# Sensors.net
KiCad netlist of a schematic drawn in Altium Designer
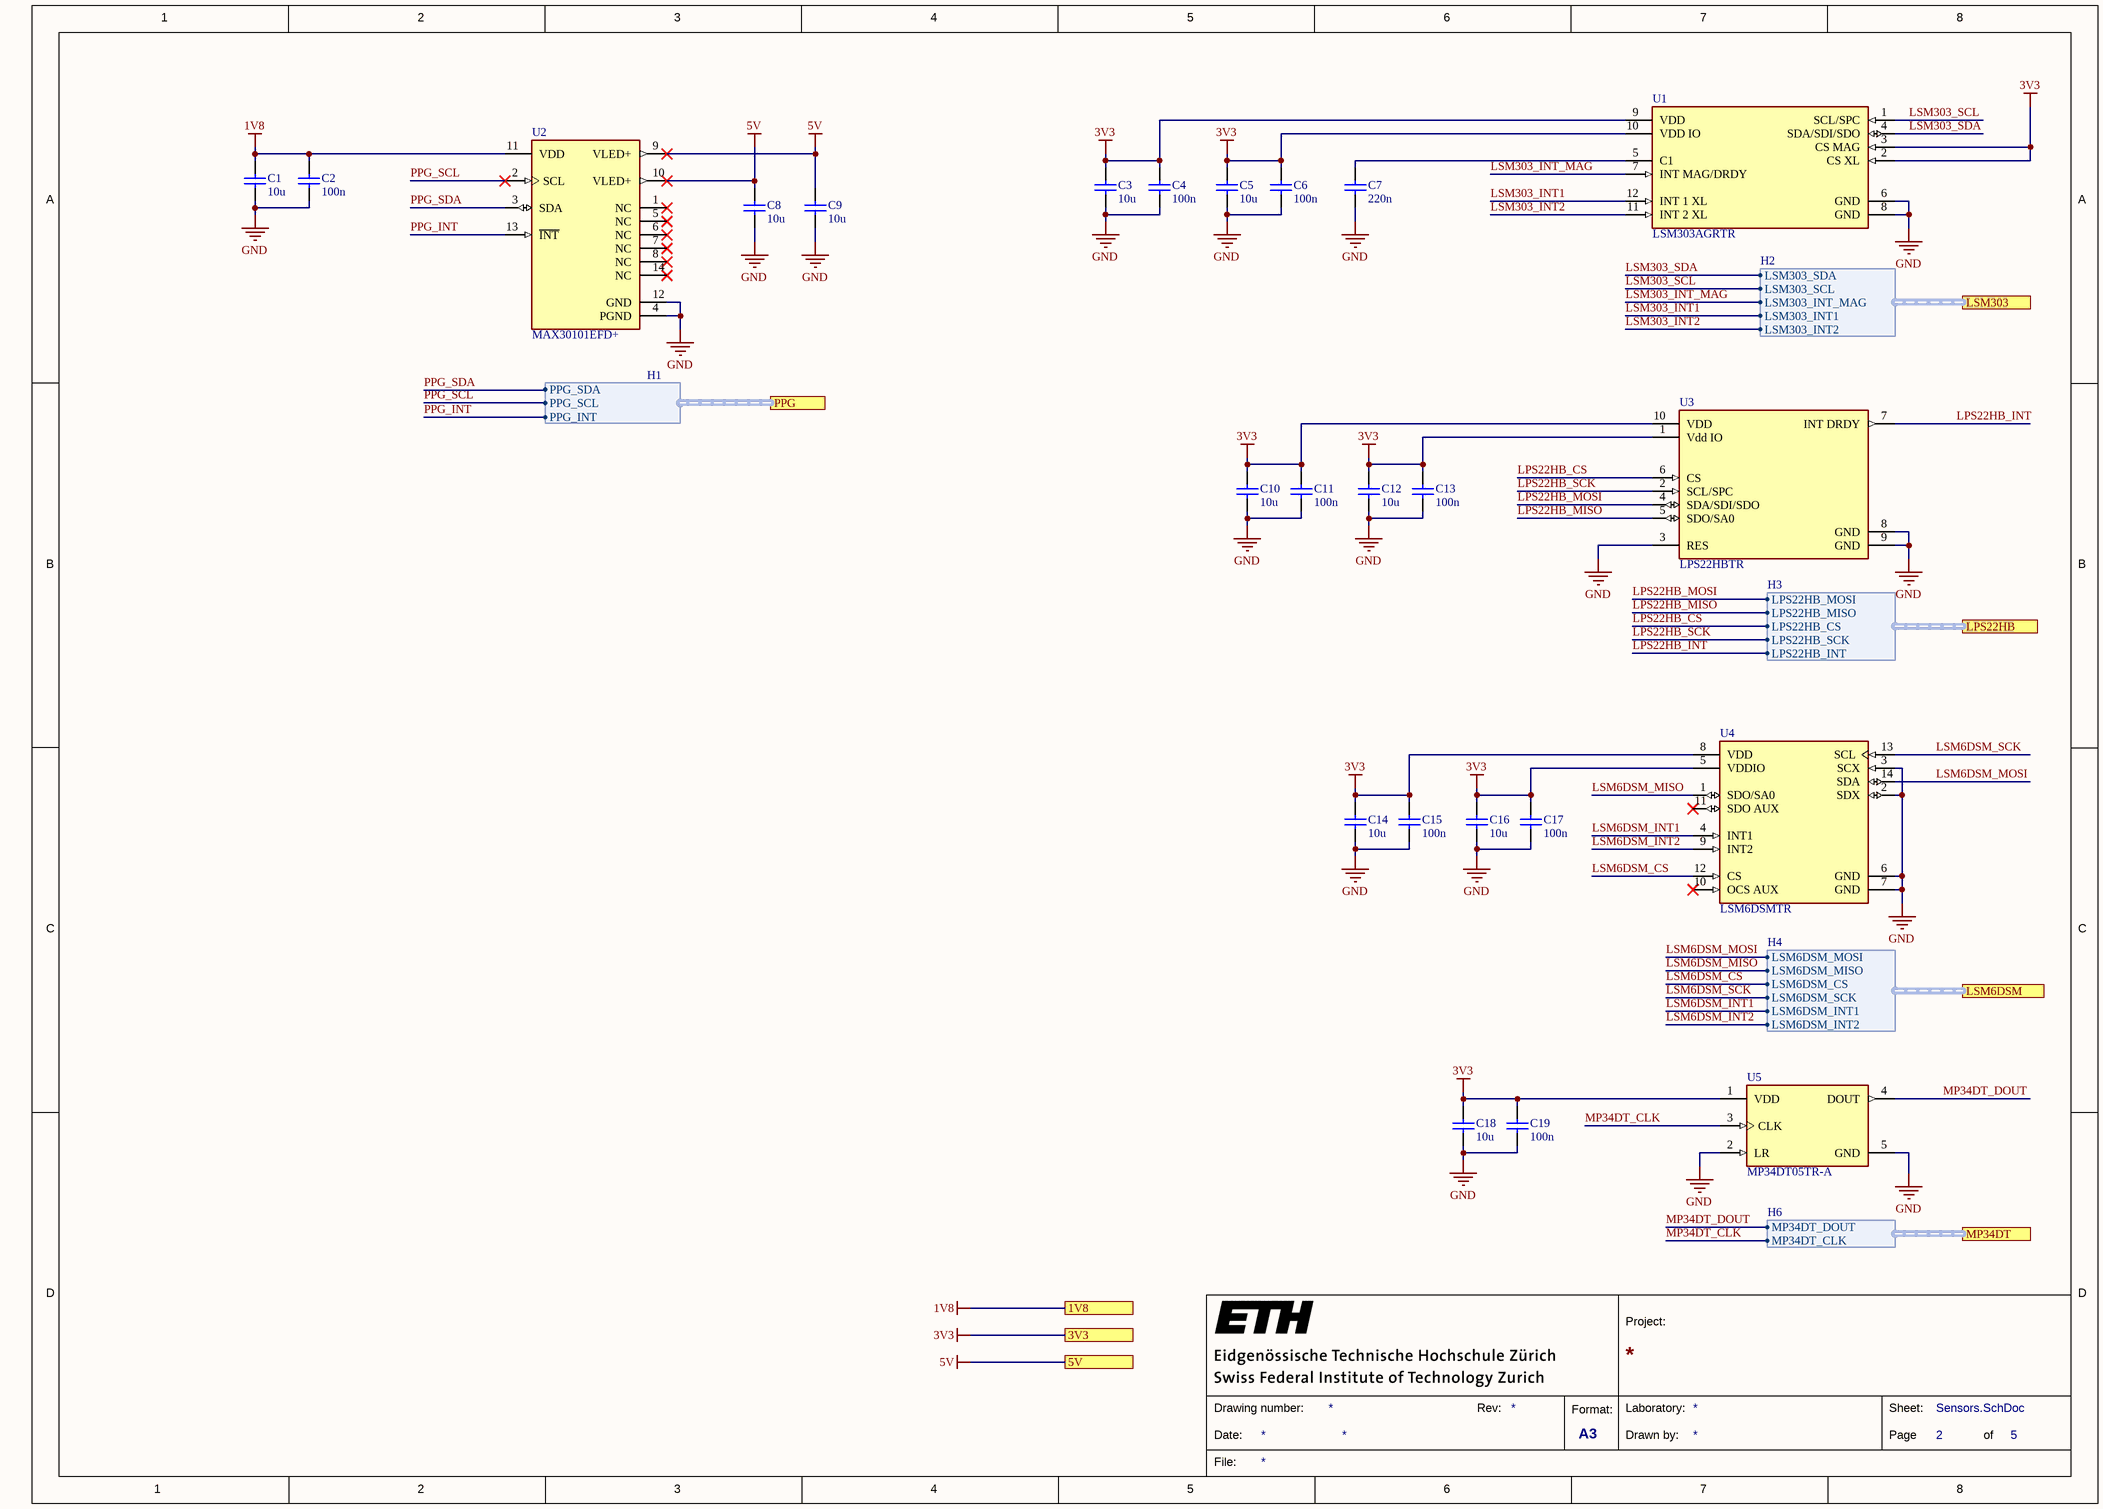
[diagram p0: Sensors.SchDoc]

(export (version "E")
  (design (tool "Eeschema 10.0.6"))
  (components
    (comp (ref "C1")
      (value "10u")
      (footprint "CAPC1005X70X10NL05")
      (description "Chip Capacitor, 10 uF, +/- 20%, -55 to 85 degC, 0402 (1005 Metric), RoHS, Tape and Reel")
      (fields
        (field (name "PCN PART NUMBER") "MLCCPartNumberChange30/Nov/2012")
        (field (name "TOLERANCE") "±20%")
      )
      (libsource (lib "Altium Content Vault") (part "CAP-NP-2"))
    )
    (comp (ref "C2")
      (value "100n")
      (footprint "CAPC1005X60X30ML05T10")
      (fields (field (name "MANUFACTURER") "Kemet") (field (name "PART NUMBER") "C0402C104K8PACTU"))
      (libsource (lib "Altium Content Vault") (part "CAP"))
    )
    (comp (ref "C3")
      (value "10u")
      (footprint "CAPC1005X70X10NL05")
      (description "Chip Capacitor, 10 uF, +/- 20%, -55 to 85 degC, 0402 (1005 Metric), RoHS, Tape and Reel")
      (fields
        (field (name "PCN PART NUMBER") "MLCCPartNumberChange30/Nov/2012")
        (field (name "TOLERANCE") "±20%")
      )
      (libsource (lib "Altium Content Vault") (part "CAP-NP-2"))
    )
    (comp (ref "C4")
      (value "100n")
      (footprint "CAPC1005X60X30ML05T10")
      (fields (field (name "MANUFACTURER") "Kemet") (field (name "PART NUMBER") "C0402C104K8PACTU"))
      (libsource (lib "Altium Content Vault") (part "CAP"))
    )
    (comp (ref "C5")
      (value "10u")
      (footprint "CAPC1005X70X10NL05")
      (description "Chip Capacitor, 10 uF, +/- 20%, -55 to 85 degC, 0402 (1005 Metric), RoHS, Tape and Reel")
      (fields
        (field (name "PCN PART NUMBER") "MLCCPartNumberChange30/Nov/2012")
        (field (name "TOLERANCE") "±20%")
      )
      (libsource (lib "Altium Content Vault") (part "CAP-NP-2"))
    )
    (comp (ref "C6")
      (value "100n")
      (footprint "CAPC1005X60X30ML05T10")
      (fields (field (name "MANUFACTURER") "Kemet") (field (name "PART NUMBER") "C0402C104K8PACTU"))
      (libsource (lib "Altium Content Vault") (part "CAP"))
    )
    (comp (ref "C7")
      (value "220n")
      (footprint "CAPC1005X55X25ML05T10")
      (description "Chip Capacitor, 220 nF, +/- 10%, 16 V, -55 to 125 degC, 0402 (1005 Metric), RoHS, Tape and Reel")
      (fields (field (name "MANUFACTURER") "Murata"))
      (libsource (lib "Altium Content Vault") (part "CAP-NP-2"))
    )
    (comp (ref "C8")
      (value "10u")
      (footprint "CAPC1005X70X10NL05")
      (description "Chip Capacitor, 10 uF, +/- 20%, -55 to 85 degC, 0402 (1005 Metric), RoHS, Tape and Reel")
      (fields
        (field (name "PCN PART NUMBER") "MLCCPartNumberChange30/Nov/2012")
        (field (name "TOLERANCE") "±20%")
      )
      (libsource (lib "Altium Content Vault") (part "CAP-NP-2"))
    )
    (comp (ref "C9")
      (value "10u")
      (footprint "CAPC1005X70X10NL05")
      (description "Chip Capacitor, 10 uF, +/- 20%, -55 to 85 degC, 0402 (1005 Metric), RoHS, Tape and Reel")
      (fields
        (field (name "PCN PART NUMBER") "MLCCPartNumberChange30/Nov/2012")
        (field (name "TOLERANCE") "±20%")
      )
      (libsource (lib "Altium Content Vault") (part "CAP-NP-2"))
    )
    (comp (ref "C10")
      (value "10u")
      (footprint "CAPC1005X70X10NL05")
      (description "Chip Capacitor, 10 uF, +/- 20%, -55 to 85 degC, 0402 (1005 Metric), RoHS, Tape and Reel")
      (fields
        (field (name "PCN PART NUMBER") "MLCCPartNumberChange30/Nov/2012")
        (field (name "TOLERANCE") "±20%")
      )
      (libsource (lib "Altium Content Vault") (part "CAP-NP-2"))
    )
    (comp (ref "C11")
      (value "100n")
      (footprint "CAPC1005X60X30ML05T10")
      (fields (field (name "MANUFACTURER") "Kemet") (field (name "PART NUMBER") "C0402C104K8PACTU"))
      (libsource (lib "Altium Content Vault") (part "CAP"))
    )
    (comp (ref "C12")
      (value "10u")
      (footprint "CAPC1005X70X10NL05")
      (description "Chip Capacitor, 10 uF, +/- 20%, -55 to 85 degC, 0402 (1005 Metric), RoHS, Tape and Reel")
      (fields
        (field (name "PCN PART NUMBER") "MLCCPartNumberChange30/Nov/2012")
        (field (name "TOLERANCE") "±20%")
      )
      (libsource (lib "Altium Content Vault") (part "CAP-NP-2"))
    )
    (comp (ref "C13")
      (value "100n")
      (footprint "CAPC1005X60X30ML05T10")
      (fields (field (name "MANUFACTURER") "Kemet") (field (name "PART NUMBER") "C0402C104K8PACTU"))
      (libsource (lib "Altium Content Vault") (part "CAP"))
    )
    (comp (ref "C14")
      (value "10u")
      (footprint "CAPC1005X70X10NL05")
      (description "Chip Capacitor, 10 uF, +/- 20%, -55 to 85 degC, 0402 (1005 Metric), RoHS, Tape and Reel")
      (fields
        (field (name "PCN PART NUMBER") "MLCCPartNumberChange30/Nov/2012")
        (field (name "TOLERANCE") "±20%")
      )
      (libsource (lib "Altium Content Vault") (part "CAP-NP-2"))
    )
    (comp (ref "C15")
      (value "100n")
      (footprint "CAPC1005X60X30ML05T10")
      (fields (field (name "MANUFACTURER") "Kemet") (field (name "PART NUMBER") "C0402C104K8PACTU"))
      (libsource (lib "Altium Content Vault") (part "CAP"))
    )
    (comp (ref "C16")
      (value "10u")
      (footprint "CAPC1005X70X10NL05")
      (description "Chip Capacitor, 10 uF, +/- 20%, -55 to 85 degC, 0402 (1005 Metric), RoHS, Tape and Reel")
      (fields
        (field (name "PCN PART NUMBER") "MLCCPartNumberChange30/Nov/2012")
        (field (name "TOLERANCE") "±20%")
      )
      (libsource (lib "Altium Content Vault") (part "CAP-NP-2"))
    )
    (comp (ref "C17")
      (value "100n")
      (footprint "CAPC1005X60X30ML05T10")
      (fields (field (name "MANUFACTURER") "Kemet") (field (name "PART NUMBER") "C0402C104K8PACTU"))
      (libsource (lib "Altium Content Vault") (part "CAP"))
    )
    (comp (ref "C18")
      (value "10u")
      (footprint "CAPC1005X70X10NL05")
      (description "Chip Capacitor, 10 uF, +/- 20%, -55 to 85 degC, 0402 (1005 Metric), RoHS, Tape and Reel")
      (fields
        (field (name "PCN PART NUMBER") "MLCCPartNumberChange30/Nov/2012")
        (field (name "TOLERANCE") "±20%")
      )
      (libsource (lib "Altium Content Vault") (part "CAP-NP-2"))
    )
    (comp (ref "C19")
      (value "100n")
      (footprint "CAPC1005X60X30ML05T10")
      (fields (field (name "MANUFACTURER") "Kemet") (field (name "PART NUMBER") "C0402C104K8PACTU"))
      (libsource (lib "Altium Content Vault") (part "CAP"))
    )
    (comp (ref "U1")
      (value "LSM303AGRTR")
      (footprint "FP-LGA-12-8487206-MFG")
      (description "IMU ACCEL/MAG I2C/SPI 12LGA")
      (fields
        (field (name "OCTOPART") "https://octopart.com/lsm303agrtr-stmicroelectronics-59386630")
        (field (name "MANUFACTURER") "STMicroelectronics")
      )
      (libsource (lib "Altium Content Vault") (part "dfb71b4f0b3d4bd25037e938b2e7b05"))
    )
    (comp (ref "U2")
      (value "MAX30101EFD+")
      (footprint "FP-F143A5-1-MFG")
      (description "INTEGRATED OPTICAL SENSOR")
      (fields
        (field (name "MANUFACTURER") "Maxim Integrated")
        (field (name "OCTOPART") "https://octopart.com/max30101efd%2B-maxim+integrated-57054333")
      )
      (libsource (lib "Altium Content Vault") (part "7412f82398c18c21c59cad441ae59a4"))
    )
    (comp (ref "U3")
      (value "LPS22HBTR")
      (footprint "FP-HLGA-10L-8479831-0")
      (description "MEMS NANO PRESSURE SENSOR: 260-1")
      (fields
        (field (name "OCTOPART") "https://octopart.com/lps22hbtr-stmicroelectronics-51851131")
        (field (name "MANUFACTURER") "STMicroelectronics")
      )
      (libsource (lib "Altium Content Vault") (part "d4c28707ea3ba579869663dd93796c5"))
    )
    (comp (ref "U4")
      (value "LSM6DSMTR")
      (footprint "FP-LGA-14L-DM00249496-MFG")
      (description "IMU ACCEL/GYRO I2C/SPI 14LGA")
      (fields
        (field (name "OCTOPART") "https://octopart.com/lsm6dsmtr-stmicroelectronics-66358194")
        (field (name "MANUFACTURER") "STMicroelectronics")
      )
      (libsource (lib "Altium Content Vault") (part "dd82ae232bae541fa9c740d21cb9072"))
    )
    (comp (ref "U5")
      (value "MP34DT05TR-A")
      (footprint "FP-HCLGA-DM00231908-MFG")
      (description "MEMS AUD MIC SENSOR OMNI 4HCLGA")
      (fields
        (field (name "OCTOPART") "https://octopart.com/mp34dt05tr-a-stmicroelectronics-87879016")
        (field (name "MANUFACTURER") "STMicroelectronics")
      )
      (libsource (lib "Altium Content Vault") (part "b42018b50dcec9466a4e70146be022e"))
    )
  )
  (nets
    (net (code "7") (name "/LPS22HB_CS") (class "Default")
      (node (ref "U3") (pin "6") (pinfunction "CS_6") (pintype "input"))
    )
    (net (code "8") (name "/LPS22HB_INT") (class "Default")
      (node (ref "U3") (pin "7") (pinfunction "INT_DRDY_7") (pintype "output"))
    )
    (net (code "9") (name "/LPS22HB_MISO") (class "Default")
      (node (ref "U3") (pin "5") (pinfunction "SDO/SA0_5") (pintype "bidirectional"))
    )
    (net (code "10") (name "/LPS22HB_MOSI") (class "Default")
      (node (ref "U3") (pin "4") (pinfunction "SDA/SDI/SDO_4") (pintype "bidirectional"))
    )
    (net (code "11") (name "/LPS22HB_SCK") (class "Default")
      (node (ref "U3") (pin "2") (pinfunction "SCL/SPC_2") (pintype "input"))
    )
    (net (code "12") (name "/LSM6DSM_CS") (class "Default")
      (node (ref "U4") (pin "12") (pinfunction "CS_12") (pintype "input"))
    )
    (net (code "13") (name "/LSM6DSM_INT1") (class "Default")
      (node (ref "U4") (pin "4") (pinfunction "INT1_4") (pintype "input"))
    )
    (net (code "14") (name "/LSM6DSM_INT2") (class "Default")
      (node (ref "U4") (pin "9") (pinfunction "INT2_9") (pintype "input"))
    )
    (net (code "15") (name "/LSM6DSM_MISO") (class "Default")
      (node (ref "U4") (pin "1") (pinfunction "SDO/SA0_1") (pintype "bidirectional"))
    )
    (net (code "16") (name "/LSM6DSM_MOSI") (class "Default")
      (node (ref "U4") (pin "14") (pinfunction "SDA_14") (pintype "bidirectional"))
    )
    (net (code "17") (name "/LSM6DSM_SCK") (class "Default")
      (node (ref "U4") (pin "13") (pinfunction "SCL_13") (pintype "input"))
    )
    (net (code "18") (name "/LSM303_INT1") (class "Default")
      (node (ref "U1") (pin "12") (pinfunction "INT_1_XL_12") (pintype "input"))
    )
    (net (code "19") (name "/LSM303_INT2") (class "Default")
      (node (ref "U1") (pin "11") (pinfunction "INT_2_XL_11") (pintype "input"))
    )
    (net (code "20") (name "/LSM303_INT_MAG") (class "Default")
      (node (ref "U1") (pin "7") (pinfunction "INT_MAG/DRDY_7") (pintype "input"))
    )
    (net (code "21") (name "/LSM303_SCL") (class "Default")
      (node (ref "U1") (pin "1") (pinfunction "SCL/SPC_1") (pintype "input"))
    )
    (net (code "22") (name "/LSM303_SDA") (class "Default")
      (node (ref "U1") (pin "4") (pinfunction "SDA/SDI/SDO_4") (pintype "bidirectional"))
    )
    (net (code "23") (name "/MP34DT_CLK") (class "Default")
      (node (ref "U5") (pin "3") (pinfunction "CLK_3") (pintype "input"))
    )
    (net (code "24") (name "/MP34DT_DOUT") (class "Default")
      (node (ref "U5") (pin "4") (pinfunction "DOUT_4") (pintype "output"))
    )
    (net (code "25") (name "/PPG_INT") (class "Default")
      (node (ref "U2") (pin "13") (pinfunction "~{INT}_13") (pintype "input"))
    )
    (net (code "26") (name "/PPG_SCL") (class "Default")
      (node (ref "U2") (pin "2") (pinfunction "SCL_2") (pintype "input"))
    )
    (net (code "27") (name "/PPG_SDA") (class "Default")
      (node (ref "U2") (pin "3") (pinfunction "SDA_3") (pintype "bidirectional"))
    )
    (net (code "33") (name "1V8") (class "Default")
      (node (ref "C1") (pin "2") (pinfunction "2_2") (pintype "passive"))
      (node (ref "C2") (pin "2") (pinfunction "2_2") (pintype "passive"))
      (node (ref "U2") (pin "11") (pinfunction "VDD_11") (pintype "power_in"))
    )
    (net (code "34") (name "3V3") (class "Default")
      (node (ref "C10") (pin "2") (pinfunction "2_2") (pintype "passive"))
      (node (ref "C11") (pin "2") (pinfunction "2_2") (pintype "passive"))
      (node (ref "C12") (pin "2") (pinfunction "2_2") (pintype "passive"))
      (node (ref "C13") (pin "2") (pinfunction "2_2") (pintype "passive"))
      (node (ref "C14") (pin "2") (pinfunction "2_2") (pintype "passive"))
      (node (ref "C15") (pin "2") (pinfunction "2_2") (pintype "passive"))
      (node (ref "C16") (pin "2") (pinfunction "2_2") (pintype "passive"))
      (node (ref "C17") (pin "2") (pinfunction "2_2") (pintype "passive"))
      (node (ref "C18") (pin "2") (pinfunction "2_2") (pintype "passive"))
      (node (ref "C19") (pin "2") (pinfunction "2_2") (pintype "passive"))
      (node (ref "C3") (pin "2") (pinfunction "2_2") (pintype "passive"))
      (node (ref "C4") (pin "2") (pinfunction "2_2") (pintype "passive"))
      (node (ref "C5") (pin "2") (pinfunction "2_2") (pintype "passive"))
      (node (ref "C6") (pin "2") (pinfunction "2_2") (pintype "passive"))
      (node (ref "U1") (pin "10") (pinfunction "VDD_IO_10") (pintype "power_in"))
      (node (ref "U1") (pin "2") (pinfunction "CS_XL_2") (pintype "input"))
      (node (ref "U1") (pin "3") (pinfunction "CS_MAG_3") (pintype "input"))
      (node (ref "U1") (pin "9") (pinfunction "VDD_9") (pintype "power_in"))
      (node (ref "U3") (pin "1") (pinfunction "Vdd_IO_1") (pintype "power_in"))
      (node (ref "U3") (pin "10") (pinfunction "VDD_10") (pintype "power_in"))
      (node (ref "U4") (pin "5") (pinfunction "VDDIO_5") (pintype "power_in"))
      (node (ref "U4") (pin "8") (pinfunction "VDD_8") (pintype "power_in"))
      (node (ref "U5") (pin "1") (pinfunction "VDD_1") (pintype "power_in"))
    )
    (net (code "35") (name "5V") (class "Default")
      (node (ref "C8") (pin "2") (pinfunction "2_2") (pintype "passive"))
      (node (ref "C9") (pin "2") (pinfunction "2_2") (pintype "passive"))
      (node (ref "U2") (pin "10") (pinfunction "VLED+_10") (pintype "output"))
      (node (ref "U2") (pin "9") (pinfunction "VLED+_9") (pintype "output"))
    )
    (net (code "36") (name "GND") (class "Default")
      (node (ref "C1") (pin "1") (pinfunction "1_1") (pintype "passive"))
      (node (ref "C10") (pin "1") (pinfunction "1_1") (pintype "passive"))
      (node (ref "C11") (pin "1") (pinfunction "1_1") (pintype "passive"))
      (node (ref "C12") (pin "1") (pinfunction "1_1") (pintype "passive"))
      (node (ref "C13") (pin "1") (pinfunction "1_1") (pintype "passive"))
      (node (ref "C14") (pin "1") (pinfunction "1_1") (pintype "passive"))
      (node (ref "C15") (pin "1") (pinfunction "1_1") (pintype "passive"))
      (node (ref "C16") (pin "1") (pinfunction "1_1") (pintype "passive"))
      (node (ref "C17") (pin "1") (pinfunction "1_1") (pintype "passive"))
      (node (ref "C18") (pin "1") (pinfunction "1_1") (pintype "passive"))
      (node (ref "C19") (pin "1") (pinfunction "1_1") (pintype "passive"))
      (node (ref "C2") (pin "1") (pinfunction "1_1") (pintype "passive"))
      (node (ref "C3") (pin "1") (pinfunction "1_1") (pintype "passive"))
      (node (ref "C4") (pin "1") (pinfunction "1_1") (pintype "passive"))
      (node (ref "C5") (pin "1") (pinfunction "1_1") (pintype "passive"))
      (node (ref "C6") (pin "1") (pinfunction "1_1") (pintype "passive"))
      (node (ref "C7") (pin "1") (pinfunction "1_1") (pintype "passive"))
      (node (ref "C8") (pin "1") (pinfunction "1_1") (pintype "passive"))
      (node (ref "C9") (pin "1") (pinfunction "1_1") (pintype "passive"))
      (node (ref "U1") (pin "6") (pinfunction "GND_6") (pintype "power_in"))
      (node (ref "U1") (pin "8") (pinfunction "GND_8") (pintype "power_in"))
      (node (ref "U2") (pin "12") (pinfunction "GND_12") (pintype "power_in"))
      (node (ref "U2") (pin "4") (pinfunction "PGND_4") (pintype "power_in"))
      (node (ref "U3") (pin "3") (pinfunction "RES_3") (pintype "passive"))
      (node (ref "U3") (pin "8") (pinfunction "GND_8") (pintype "power_in"))
      (node (ref "U3") (pin "9") (pinfunction "GND_9") (pintype "power_in"))
      (node (ref "U4") (pin "2") (pinfunction "SDX_2") (pintype "bidirectional"))
      (node (ref "U4") (pin "3") (pinfunction "SCX_3") (pintype "input"))
      (node (ref "U4") (pin "6") (pinfunction "GND_6") (pintype "power_in"))
      (node (ref "U4") (pin "7") (pinfunction "GND_7") (pintype "power_in"))
      (node (ref "U5") (pin "2") (pinfunction "LR_2") (pintype "input"))
      (node (ref "U5") (pin "5") (pinfunction "GND_5") (pintype "power_in"))
    )
    (net (code "37") (name "Net-(U1-C1)") (class "Default")
      (node (ref "C7") (pin "2") (pinfunction "2_2") (pintype "passive"))
      (node (ref "U1") (pin "5") (pinfunction "C1_5") (pintype "passive"))
    )
    (net (code "38") (name "unconnected-(U2-NC-Pad1)") (class "Default")
      (node (ref "U2") (pin "1") (pinfunction "NC_1") (pintype "passive+no_connect"))
    )
    (net (code "39") (name "unconnected-(U2-NC-Pad5)") (class "Default")
      (node (ref "U2") (pin "5") (pinfunction "NC_5") (pintype "passive+no_connect"))
    )
    (net (code "40") (name "unconnected-(U2-NC-Pad6)") (class "Default")
      (node (ref "U2") (pin "6") (pinfunction "NC_6") (pintype "passive+no_connect"))
    )
    (net (code "41") (name "unconnected-(U2-NC-Pad7)") (class "Default")
      (node (ref "U2") (pin "7") (pinfunction "NC_7") (pintype "passive+no_connect"))
    )
    (net (code "42") (name "unconnected-(U2-NC-Pad8)") (class "Default")
      (node (ref "U2") (pin "8") (pinfunction "NC_8") (pintype "passive+no_connect"))
    )
    (net (code "43") (name "unconnected-(U2-NC-Pad14)") (class "Default")
      (node (ref "U2") (pin "14") (pinfunction "NC_14") (pintype "passive+no_connect"))
    )
    (net (code "44") (name "unconnected-(U4-OCS_AUX-Pad10)") (class "Default")
      (node (ref "U4") (pin "10") (pinfunction "OCS_AUX_10") (pintype "input+no_connect"))
    )
    (net (code "45") (name "unconnected-(U4-SDO_AUX-Pad11)") (class "Default")
      (node (ref "U4") (pin "11") (pinfunction "SDO_AUX_11") (pintype "bidirectional+no_connect"))
    )
  )
)
